# 12Vto5V_3A.net
KiCad netlist of a schematic drawn in Altium Designer
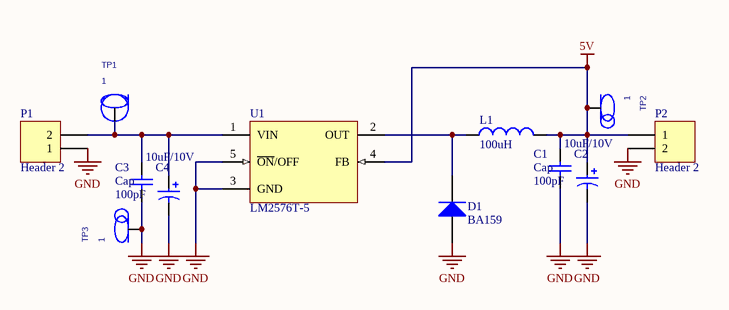
[diagram p0: 12Vto5V_3A.SchDoc]

(export (version "E")
  (design (tool "Eeschema 10.0.6"))
  (components
    (comp (ref "C1")
      (value "Cap")
      (footprint "CAPR2.54-5.1x3.2")
      (description "Capacitor")
      (fields (field (name "ALTIUM_VALUE") "100pF") (field (name "PUBLISHER") "Altium Limited"))
      (libsource (lib "Miscellaneous Devices") (part "Cap"))
    )
    (comp (ref "C2")
      (value "10uF/10V")
      (footprint "ECAP")
      (description "Bi-Polar Capacitor")
      (libsource (lib "*") (part "CAP2"))
    )
    (comp (ref "C3")
      (value "Cap")
      (footprint "CAPR2.54-5.1x3.2")
      (description "Capacitor")
      (fields (field (name "ALTIUM_VALUE") "100pF") (field (name "PUBLISHER") "Altium Limited"))
      (libsource (lib "Miscellaneous Devices") (part "Cap"))
    )
    (comp (ref "C4")
      (value "10uF/10V")
      (footprint "ECAP")
      (description "Bi-Polar Capacitor")
      (libsource (lib "*") (part "CAP2"))
    )
    (comp (ref "D1")
      (value "BA159")
      (footprint "DIO7.1-3.9x1.9")
      (description "High Conductance Fast Diode")
      (fields (field (name "PUBLISHER") "Altium Limited"))
      (libsource (lib "Miscellaneous Devices") (part "Diode 1N914"))
    )
    (comp (ref "L1")
      (value "100uH")
      (description "Inductor")
      (fields (field (name "PUBLISHER") "Altium Limited"))
      (libsource (lib "LIB-REF_SCH") (part "Inductor"))
    )
    (comp (ref "P1")
      (value "Header 2")
      (footprint "HDR1X2")
      (description "Header, 2-Pin")
      (fields (field (name "PUBLISHER") "Altium Limited"))
      (libsource (lib "Miscellaneous Connectors") (part "Header 2"))
    )
    (comp (ref "P2")
      (value "Header 2")
      (footprint "HDR1X2")
      (description "Header, 2-Pin")
      (fields (field (name "PUBLISHER") "Altium Limited"))
      (libsource (lib "") (part "Header 2_1"))
    )
    (comp (ref "TP1") (value "1") (footprint "itp") (libsource (lib "*") (part "TP")))
    (comp (ref "TP2") (value "1") (footprint "itp") (libsource (lib "*") (part "TP")))
    (comp (ref "TP3") (value "1") (footprint "itp") (libsource (lib "*") (part "TP")))
    (comp (ref "U1")
      (value "LM2576T-5")
      (footprint "TO220_5")
      (description "SIMPLE SWITCHER; 3A Step-Down Voltage Regulator")
      (fields
        (field (name "PARTNUMBER") "LM2576T-ADJ")
        (field (name "MANUFACTURER") "National Semiconductor")
        (field (name "PUBLISHER") "Altium Limited")
      )
      (libsource (lib "NSC Switcher") (part "LM2576T-ADJ"))
    )
  )
  (nets
    (net (code "1") (name "5V") (class "Default")
      (node (ref "C1") (pin "2") (pinfunction "2_2") (pintype "passive"))
      (node (ref "C2") (pin "1") (pinfunction "1_1") (pintype "passive"))
      (node (ref "L1") (pin "2") (pinfunction "2_2") (pintype "passive"))
      (node (ref "P2") (pin "1") (pinfunction "1_1") (pintype "passive"))
      (node (ref "TP2") (pin "1") (pinfunction "1_1") (pintype "passive"))
      (node (ref "U1") (pin "4") (pinfunction "FB_4") (pintype "input"))
    )
    (net (code "2") (name "GND") (class "Default")
      (node (ref "C1") (pin "1") (pinfunction "1_1") (pintype "passive"))
      (node (ref "C2") (pin "2") (pinfunction "2_2") (pintype "passive"))
      (node (ref "C3") (pin "1") (pinfunction "1_1") (pintype "passive"))
      (node (ref "C4") (pin "2") (pinfunction "2_2") (pintype "passive"))
      (node (ref "D1") (pin "1") (pinfunction "A_1") (pintype "passive"))
      (node (ref "P1") (pin "1") (pinfunction "1_1") (pintype "passive"))
      (node (ref "P2") (pin "2") (pinfunction "2_2") (pintype "passive"))
      (node (ref "TP3") (pin "1") (pinfunction "1_1") (pintype "passive"))
      (node (ref "U1") (pin "3") (pinfunction "GND_3") (pintype "power_in"))
      (node (ref "U1") (pin "5") (pinfunction "~{ON}/OFF_5") (pintype "input"))
    )
    (net (code "3") (name "Net-(D1-K)") (class "Default")
      (node (ref "D1") (pin "2") (pinfunction "K_2") (pintype "passive"))
      (node (ref "L1") (pin "1") (pinfunction "1_1") (pintype "passive"))
      (node (ref "U1") (pin "2") (pinfunction "OUT_2") (pintype "power_in"))
    )
    (net (code "4") (name "Net-(U1-VIN)") (class "Default")
      (node (ref "C3") (pin "2") (pinfunction "2_2") (pintype "passive"))
      (node (ref "C4") (pin "1") (pinfunction "1_1") (pintype "passive"))
      (node (ref "P1") (pin "2") (pinfunction "2_2") (pintype "passive"))
      (node (ref "TP1") (pin "1") (pinfunction "1_1") (pintype "passive"))
      (node (ref "U1") (pin "1") (pinfunction "VIN_1") (pintype "power_in"))
    )
  )
)
